# inout.net
KiCad netlist of a schematic drawn in Altium Designer
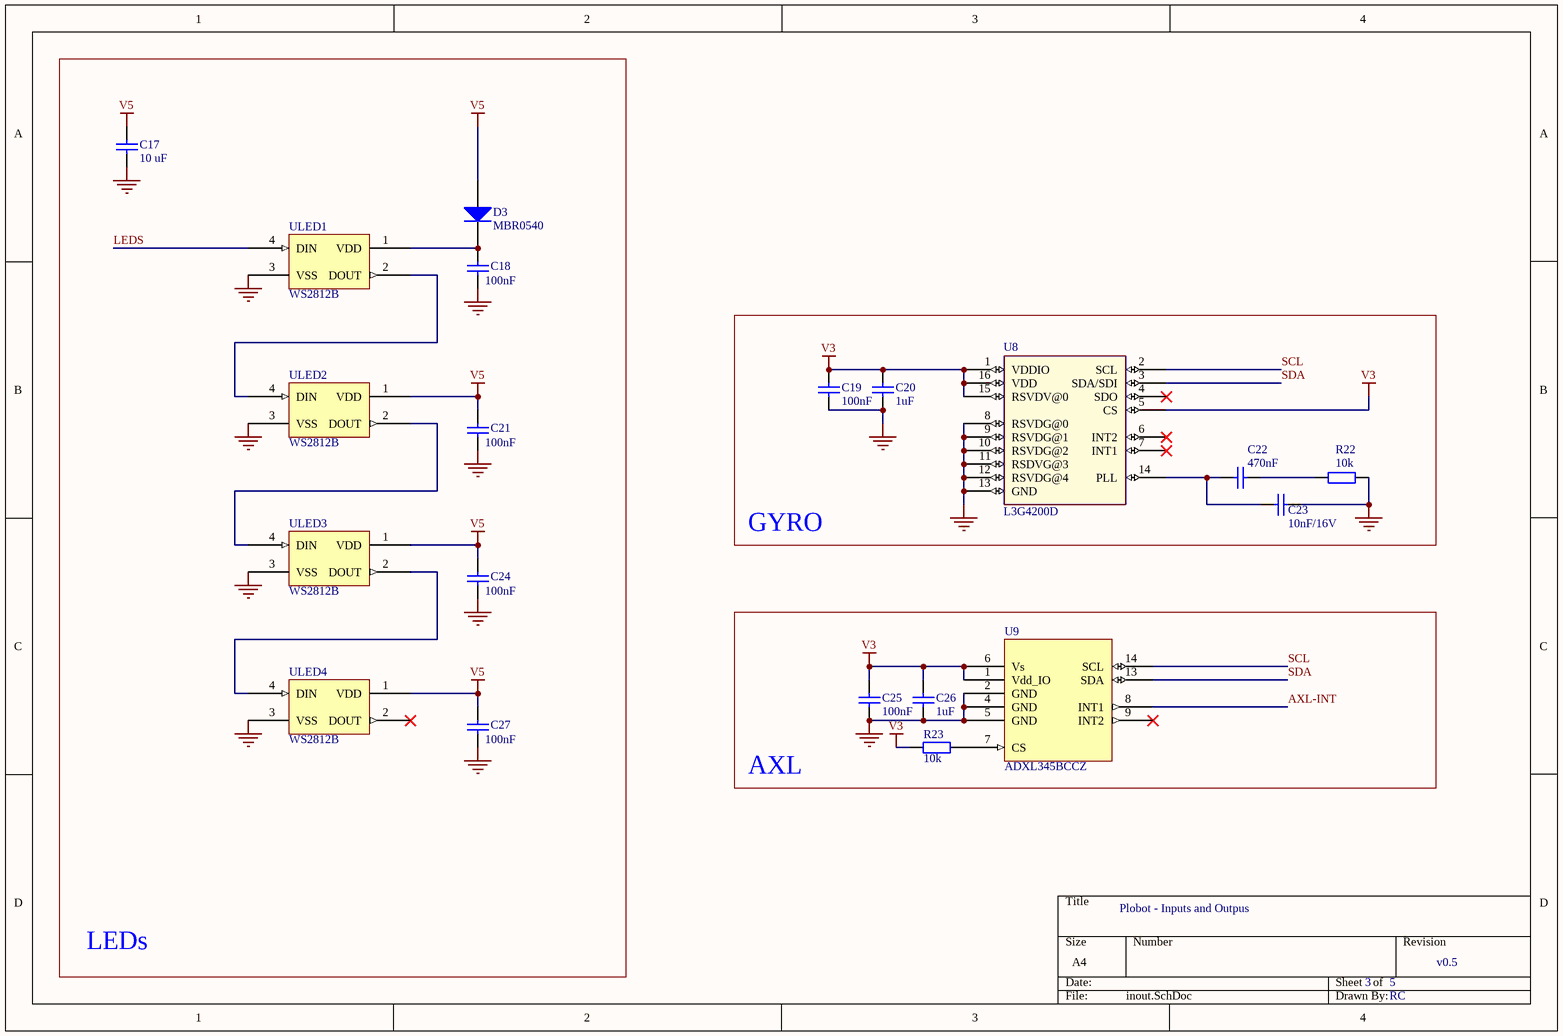
[diagram p0: inout.SchDoc]

(export (version "E")
  (design (tool "Eeschema 10.0.6"))
  (components
    (comp (ref "C17")
      (value "10 uF")
      (footprint "plobot_review:CAPC3216N")
      (description "Capacitor")
      (fields (field (name "PUBLISHER") "Altium Limited"))
      (libsource (lib "main_pcb") (part "Cap_2"))
    )
    (comp (ref "C18")
      (value "100nF")
      (footprint "plobot_review:CAPC1608N")
      (description "Capacitor")
      (fields (field (name "PUBLISHER") "Altium Limited"))
      (libsource (lib "*") (part "Cap"))
    )
    (comp (ref "C19")
      (value "100nF")
      (footprint "plobot_review:CAPC1608N")
      (description "Capacitor")
      (libsource (lib "*") (part "Cap"))
    )
    (comp (ref "C20")
      (value "1uF")
      (footprint "plobot_review:CAPC2012N")
      (description "Capacitor")
      (libsource (lib "main_pcb") (part "Cap_2"))
    )
    (comp (ref "C21")
      (value "100nF")
      (footprint "plobot_review:CAPC1608N")
      (description "Capacitor")
      (fields (field (name "PUBLISHER") "Altium Limited"))
      (libsource (lib "*") (part "Cap"))
    )
    (comp (ref "C22")
      (value "470nF")
      (footprint "plobot_review:CAPC2012N")
      (description "Capacitor")
      (libsource (lib "") (part "Cap_2_1"))
    )
    (comp (ref "C23")
      (value "10nF/16V")
      (footprint "plobot_review:CAPC2012N")
      (description "Capacitor")
      (libsource (lib "") (part "Cap_2_1"))
    )
    (comp (ref "C24")
      (value "100nF")
      (footprint "plobot_review:CAPC1608N")
      (description "Capacitor")
      (fields (field (name "PUBLISHER") "Altium Limited"))
      (libsource (lib "*") (part "Cap"))
    )
    (comp (ref "C25")
      (value "100nF")
      (footprint "plobot_review:CAPC1608N")
      (description "Capacitor")
      (fields (field (name "PUBLISHER") "Altium Limited"))
      (libsource (lib "*") (part "Cap"))
    )
    (comp (ref "C26")
      (value "1uF")
      (footprint "plobot_review:CAPC2012N")
      (description "Capacitor")
      (fields (field (name "PUBLISHER") "Altium Limited"))
      (libsource (lib "main_pcb") (part "Cap_2"))
    )
    (comp (ref "C27")
      (value "100nF")
      (footprint "plobot_review:CAPC1608N")
      (description "Capacitor")
      (fields (field (name "PUBLISHER") "Altium Limited"))
      (libsource (lib "*") (part "Cap"))
    )
    (comp (ref "D3")
      (value "MBR0540")
      (footprint "plobot_review:SOD123/X.85")
      (description "Default Diode")
      (fields (field (name "PUBLISHER") "Altium Limited"))
      (libsource (lib "Miscellaneous Devices") (part "Diode"))
    )
    (comp (ref "R22")
      (value "10k")
      (footprint "plobot_review:RESC1608N")
      (description "Resistor")
      (libsource (lib "") (part "Res2_1"))
    )
    (comp (ref "R23")
      (value "10k")
      (footprint "plobot_review:RESC1608N")
      (description "Resistor")
      (fields (field (name "PUBLISHER") "Altium Limited"))
      (libsource (lib "*") (part "Res2"))
    )
    (comp (ref "U8")
      (value "L3G4200D")
      (footprint "plobot_review:LGA16-4X4")
      (description "L3G4200D Series 2.4 - 3.6 V Three-axis Angular Rate MEMS Motion Sensor - LGA-16")
      (libsource (lib "L3G4200D") (part "L3G4200D"))
    )
    (comp (ref "U9")
      (value "ADXL345BCCZ")
      (footprint "plobot_review:ADXL345")
      (libsource (lib "components") (part "ADXL345"))
    )
    (comp (ref "ULED1")
      (value "WS2812B")
      (footprint "plobot_review:WS2812B")
      (libsource (lib "components") (part "WS2812B"))
    )
    (comp (ref "ULED2")
      (value "WS2812B")
      (footprint "plobot_review:WS2812B")
      (libsource (lib "components") (part "WS2812B"))
    )
    (comp (ref "ULED3")
      (value "WS2812B")
      (footprint "plobot_review:WS2812B")
      (libsource (lib "components") (part "WS2812B"))
    )
    (comp (ref "ULED4")
      (value "WS2812B")
      (footprint "plobot_review:WS2812B")
      (libsource (lib "components") (part "WS2812B"))
    )
  )
  (nets
    (net (code "1") (name "/AXL-INT") (class "Default")
      (node (ref "U9") (pin "8") (pinfunction "INT1_8") (pintype "output"))
    )
    (net (code "2") (name "/LEDS") (class "Default")
      (node (ref "ULED1") (pin "4") (pinfunction "DIN_4") (pintype "input"))
    )
    (net (code "3") (name "/SCL") (class "Default")
      (node (ref "U8") (pin "2") (pinfunction "SCL_2") (pintype "bidirectional"))
      (node (ref "U9") (pin "14") (pinfunction "SCL_14") (pintype "bidirectional"))
    )
    (net (code "4") (name "/SDA") (class "Default")
      (node (ref "U8") (pin "3") (pinfunction "SDA/SDI_3") (pintype "bidirectional"))
      (node (ref "U9") (pin "13") (pinfunction "SDA_13") (pintype "bidirectional"))
    )
    (net (code "5") (name "GND") (class "Default")
      (node (ref "C17") (pin "2") (pinfunction "2_2") (pintype "passive"))
      (node (ref "C18") (pin "2") (pinfunction "2_2") (pintype "passive"))
      (node (ref "C19") (pin "2") (pinfunction "2_2") (pintype "passive"))
      (node (ref "C20") (pin "2") (pinfunction "2_2") (pintype "passive"))
      (node (ref "C21") (pin "2") (pinfunction "2_2") (pintype "passive"))
      (node (ref "C23") (pin "2") (pinfunction "2_2") (pintype "passive"))
      (node (ref "C24") (pin "2") (pinfunction "2_2") (pintype "passive"))
      (node (ref "C25") (pin "2") (pinfunction "2_2") (pintype "passive"))
      (node (ref "C26") (pin "2") (pinfunction "2_2") (pintype "passive"))
      (node (ref "C27") (pin "2") (pinfunction "2_2") (pintype "passive"))
      (node (ref "R22") (pin "2") (pinfunction "2_2") (pintype "passive"))
      (node (ref "U8") (pin "10") (pinfunction "RSVDG@2_10") (pintype "bidirectional"))
      (node (ref "U8") (pin "11") (pinfunction "RSDVG@3_11") (pintype "bidirectional"))
      (node (ref "U8") (pin "12") (pinfunction "RSVDG@4_12") (pintype "bidirectional"))
      (node (ref "U8") (pin "13") (pinfunction "GND_13") (pintype "bidirectional"))
      (node (ref "U8") (pin "8") (pinfunction "RSVDG@0_8") (pintype "bidirectional"))
      (node (ref "U8") (pin "9") (pinfunction "RSVDG@1_9") (pintype "bidirectional"))
      (node (ref "U9") (pin "2") (pinfunction "GND_2") (pintype "power_in"))
      (node (ref "U9") (pin "4") (pinfunction "GND_4") (pintype "power_in"))
      (node (ref "U9") (pin "5") (pinfunction "GND_5") (pintype "power_in"))
      (node (ref "ULED1") (pin "3") (pinfunction "VSS_3") (pintype "power_in"))
      (node (ref "ULED2") (pin "3") (pinfunction "VSS_3") (pintype "power_in"))
      (node (ref "ULED3") (pin "3") (pinfunction "VSS_3") (pintype "power_in"))
      (node (ref "ULED4") (pin "3") (pinfunction "VSS_3") (pintype "power_in"))
    )
    (net (code "6") (name "Net-(C22-Pad2)") (class "Default")
      (node (ref "C22") (pin "2") (pinfunction "2_2") (pintype "passive"))
      (node (ref "R22") (pin "1") (pinfunction "1_1") (pintype "passive"))
    )
    (net (code "7") (name "Net-(D3-K)") (class "Default")
      (node (ref "C18") (pin "1") (pinfunction "1_1") (pintype "passive"))
      (node (ref "D3") (pin "1") (pinfunction "K_1") (pintype "passive"))
      (node (ref "ULED1") (pin "1") (pinfunction "VDD_1") (pintype "power_in"))
    )
    (net (code "8") (name "Net-(U8-PLL)") (class "Default")
      (node (ref "C22") (pin "1") (pinfunction "1_1") (pintype "passive"))
      (node (ref "C23") (pin "1") (pinfunction "1_1") (pintype "passive"))
      (node (ref "U8") (pin "14") (pinfunction "PLL_14") (pintype "bidirectional"))
    )
    (net (code "9") (name "Net-(U9-CS)") (class "Default")
      (node (ref "R23") (pin "2") (pinfunction "2_2") (pintype "passive"))
      (node (ref "U9") (pin "7") (pinfunction "CS_7") (pintype "input"))
    )
    (net (code "10") (name "Net-(ULED1-DOUT)") (class "Default")
      (node (ref "ULED1") (pin "2") (pinfunction "DOUT_2") (pintype "output"))
      (node (ref "ULED2") (pin "4") (pinfunction "DIN_4") (pintype "input"))
    )
    (net (code "11") (name "Net-(ULED2-DOUT)") (class "Default")
      (node (ref "ULED2") (pin "2") (pinfunction "DOUT_2") (pintype "output"))
      (node (ref "ULED3") (pin "4") (pinfunction "DIN_4") (pintype "input"))
    )
    (net (code "12") (name "Net-(ULED3-DOUT)") (class "Default")
      (node (ref "ULED3") (pin "2") (pinfunction "DOUT_2") (pintype "output"))
      (node (ref "ULED4") (pin "4") (pinfunction "DIN_4") (pintype "input"))
    )
    (net (code "13") (name "V3") (class "Default")
      (node (ref "C19") (pin "1") (pinfunction "1_1") (pintype "passive"))
      (node (ref "C20") (pin "1") (pinfunction "1_1") (pintype "passive"))
      (node (ref "C25") (pin "1") (pinfunction "1_1") (pintype "passive"))
      (node (ref "C26") (pin "1") (pinfunction "1_1") (pintype "passive"))
      (node (ref "R23") (pin "1") (pinfunction "1_1") (pintype "passive"))
      (node (ref "U8") (pin "1") (pinfunction "VDDIO_1") (pintype "bidirectional"))
      (node (ref "U8") (pin "15") (pinfunction "RSVDV@0_15") (pintype "bidirectional"))
      (node (ref "U8") (pin "16") (pinfunction "VDD_16") (pintype "bidirectional"))
      (node (ref "U8") (pin "5") (pinfunction "CS_5") (pintype "bidirectional"))
      (node (ref "U9") (pin "1") (pinfunction "Vdd_IO_1") (pintype "power_in"))
      (node (ref "U9") (pin "6") (pinfunction "Vs_6") (pintype "power_in"))
    )
    (net (code "14") (name "V5") (class "Default")
      (node (ref "C17") (pin "1") (pinfunction "1_1") (pintype "passive"))
      (node (ref "C21") (pin "1") (pinfunction "1_1") (pintype "passive"))
      (node (ref "C24") (pin "1") (pinfunction "1_1") (pintype "passive"))
      (node (ref "C27") (pin "1") (pinfunction "1_1") (pintype "passive"))
      (node (ref "D3") (pin "2") (pinfunction "A_2") (pintype "passive"))
      (node (ref "ULED2") (pin "1") (pinfunction "VDD_1") (pintype "power_in"))
      (node (ref "ULED3") (pin "1") (pinfunction "VDD_1") (pintype "power_in"))
      (node (ref "ULED4") (pin "1") (pinfunction "VDD_1") (pintype "power_in"))
    )
    (net (code "15") (name "unconnected-(U8-INT1-Pad7)") (class "Default")
      (node (ref "U8") (pin "7") (pinfunction "INT1_7") (pintype "bidirectional+no_connect"))
    )
    (net (code "16") (name "unconnected-(U8-INT2-Pad6)") (class "Default")
      (node (ref "U8") (pin "6") (pinfunction "INT2_6") (pintype "bidirectional+no_connect"))
    )
    (net (code "17") (name "unconnected-(U8-SDO-Pad4)") (class "Default")
      (node (ref "U8") (pin "4") (pinfunction "SDO_4") (pintype "bidirectional+no_connect"))
    )
    (net (code "18") (name "unconnected-(U9-INT2-Pad9)") (class "Default")
      (node (ref "U9") (pin "9") (pinfunction "INT2_9") (pintype "output+no_connect"))
    )
    (net (code "19") (name "unconnected-(ULED4-DOUT-Pad2)") (class "Default")
      (node (ref "ULED4") (pin "2") (pinfunction "DOUT_2") (pintype "output+no_connect"))
    )
  )
)
